# sensorboard_atm_rev0.net
KiCad netlist of a schematic drawn in EAGLE
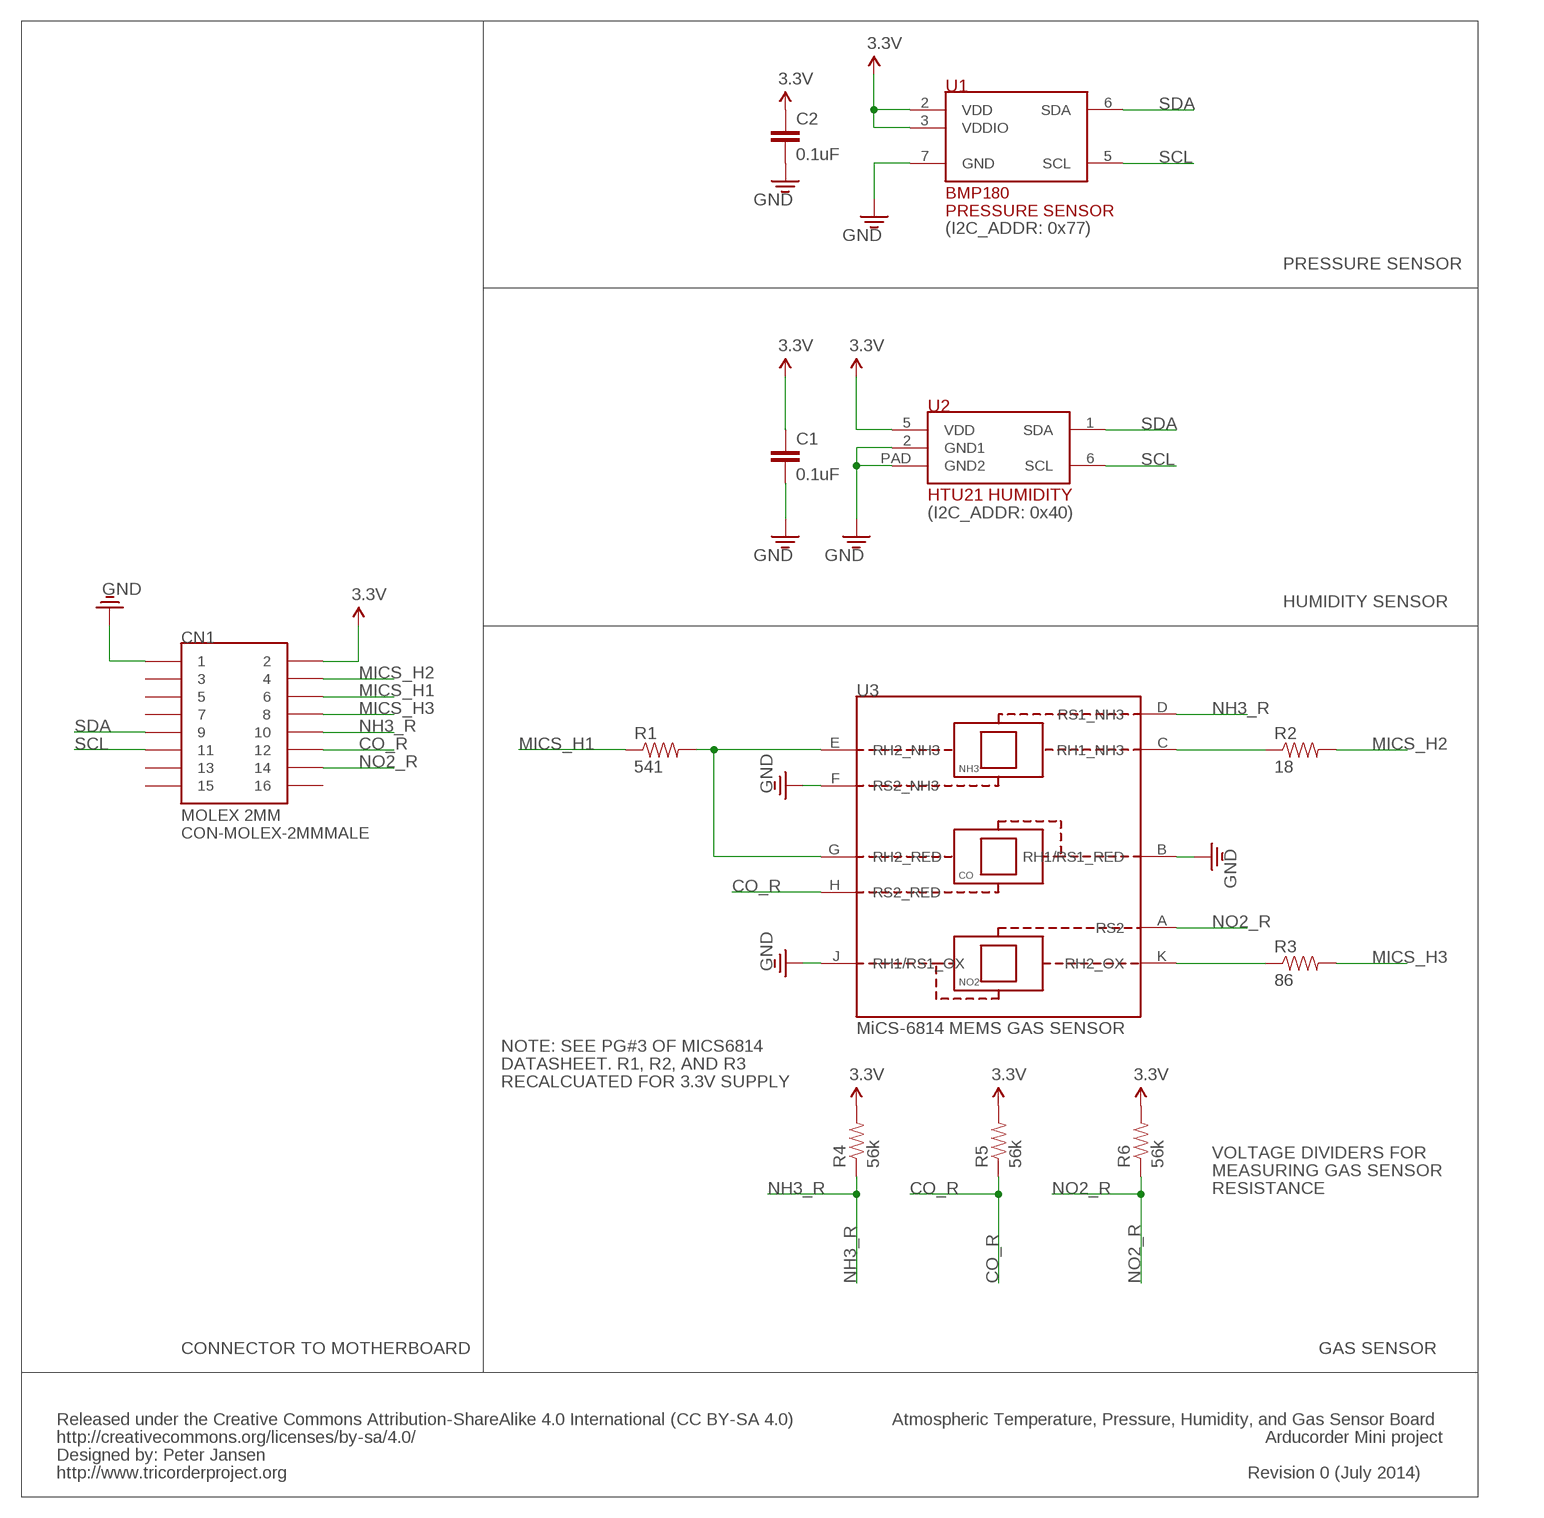
[diagram p0: schematic, sheet 1]

(export (version "E")
  (design (tool "Eeschema 10.0.6"))
  (components
    (comp (ref "C1")
      (value "0.1uF")
      (footprint "eagle-import:0603")
      (libsource (lib "eagle-import") (part "CAP0603"))
    )
    (comp (ref "C2")
      (value "0.1uF")
      (footprint "eagle-import:0603")
      (libsource (lib "eagle-import") (part "CAP0603"))
    )
    (comp (ref "CN1")
      (value "CON-MOLEX-2MMMALE")
      (footprint "eagle-import:MOLEX-0877591650")
      (libsource (lib "eagle-import") (part "CON-MOLEX-2MMMALE"))
    )
    (comp (ref "R1")
      (value "541")
      (footprint "eagle-import:0603")
      (libsource (lib "eagle-import") (part "RESISTOR0603"))
    )
    (comp (ref "R2")
      (value "18")
      (footprint "eagle-import:0603")
      (libsource (lib "eagle-import") (part "RESISTOR0603"))
    )
    (comp (ref "R3")
      (value "86")
      (footprint "eagle-import:0603")
      (libsource (lib "eagle-import") (part "RESISTOR0603"))
    )
    (comp (ref "R4")
      (value "56k")
      (footprint "eagle-import:0603")
      (libsource (lib "eagle-import") (part "RESISTOR0603"))
    )
    (comp (ref "R5")
      (value "56k")
      (footprint "eagle-import:0603")
      (libsource (lib "eagle-import") (part "RESISTOR0603"))
    )
    (comp (ref "R6")
      (value "56k")
      (footprint "eagle-import:0603")
      (libsource (lib "eagle-import") (part "RESISTOR0603"))
    )
    (comp (ref "U1")
      (value "BMP180")
      (footprint "eagle-import:BMP180")
      (libsource (lib "eagle-import") (part "BMP180"))
    )
    (comp (ref "U2")
      (value "HTU21D")
      (footprint "eagle-import:HTU21D")
      (libsource (lib "eagle-import") (part "HTU21D"))
    )
    (comp (ref "U3")
      (value "MICS-6814")
      (footprint "eagle-import:MICS-6814")
      (libsource (lib "eagle-import") (part "MICS-6814"))
    )
  )
  (nets
    (net (code "1") (name "/CO_R") (class "Default")
      (node (ref "CN1") (pin "12") (pinfunction "12_12") (pintype "bidirectional"))
      (node (ref "R5") (pin "1") (pinfunction "1_1") (pintype "passive"))
      (node (ref "U3") (pin "H") (pinfunction "RS2_RED_H") (pintype "bidirectional"))
    )
    (net (code "2") (name "/MICS_H1") (class "Default")
      (node (ref "CN1") (pin "6") (pinfunction "6_6") (pintype "bidirectional"))
      (node (ref "R1") (pin "1") (pinfunction "1_1") (pintype "passive"))
    )
    (net (code "3") (name "/MICS_H2") (class "Default")
      (node (ref "CN1") (pin "4") (pinfunction "4_4") (pintype "bidirectional"))
      (node (ref "R2") (pin "2") (pinfunction "2_2") (pintype "passive"))
    )
    (net (code "4") (name "/MICS_H3") (class "Default")
      (node (ref "CN1") (pin "8") (pinfunction "8_8") (pintype "bidirectional"))
      (node (ref "R3") (pin "2") (pinfunction "2_2") (pintype "passive"))
    )
    (net (code "5") (name "/NH3_R") (class "Default")
      (node (ref "CN1") (pin "10") (pinfunction "10_10") (pintype "bidirectional"))
      (node (ref "R4") (pin "1") (pinfunction "1_1") (pintype "passive"))
      (node (ref "U3") (pin "D") (pinfunction "RS1_NH3_D") (pintype "bidirectional"))
    )
    (net (code "6") (name "/NO2_R") (class "Default")
      (node (ref "CN1") (pin "14") (pinfunction "14_14") (pintype "bidirectional"))
      (node (ref "R6") (pin "1") (pinfunction "1_1") (pintype "passive"))
      (node (ref "U3") (pin "A") (pinfunction "RS2_A") (pintype "bidirectional"))
    )
    (net (code "7") (name "/SCL") (class "Default")
      (node (ref "CN1") (pin "11") (pinfunction "11_11") (pintype "bidirectional"))
      (node (ref "U1") (pin "5") (pinfunction "SCL_5") (pintype "bidirectional"))
      (node (ref "U2") (pin "6") (pinfunction "SCL_6") (pintype "bidirectional"))
    )
    (net (code "8") (name "/SDA") (class "Default")
      (node (ref "CN1") (pin "9") (pinfunction "9_9") (pintype "bidirectional"))
      (node (ref "U1") (pin "6") (pinfunction "SDA_6") (pintype "bidirectional"))
      (node (ref "U2") (pin "1") (pinfunction "SDA_1") (pintype "bidirectional"))
    )
    (net (code "9") (name "3.3V") (class "Default")
      (node (ref "C1") (pin "1") (pinfunction "1_1") (pintype "passive"))
      (node (ref "C2") (pin "1") (pinfunction "1_1") (pintype "passive"))
      (node (ref "CN1") (pin "2") (pinfunction "2_2") (pintype "bidirectional"))
      (node (ref "R4") (pin "2") (pinfunction "2_2") (pintype "passive"))
      (node (ref "R5") (pin "2") (pinfunction "2_2") (pintype "passive"))
      (node (ref "R6") (pin "2") (pinfunction "2_2") (pintype "passive"))
      (node (ref "U1") (pin "2") (pinfunction "VDD_2") (pintype "bidirectional"))
      (node (ref "U1") (pin "3") (pinfunction "VDDIO_3") (pintype "bidirectional"))
      (node (ref "U2") (pin "5") (pinfunction "VDD_5") (pintype "bidirectional"))
    )
    (net (code "10") (name "GND") (class "Default")
      (node (ref "C1") (pin "2") (pinfunction "2_2") (pintype "passive"))
      (node (ref "C2") (pin "2") (pinfunction "2_2") (pintype "passive"))
      (node (ref "CN1") (pin "1") (pinfunction "1_1") (pintype "bidirectional"))
      (node (ref "U1") (pin "7") (pinfunction "GND_7") (pintype "bidirectional"))
      (node (ref "U2") (pin "2") (pinfunction "GND1_2") (pintype "bidirectional"))
      (node (ref "U2") (pin "PAD") (pinfunction "GND2_PAD") (pintype "bidirectional"))
      (node (ref "U3") (pin "B") (pinfunction "RH1/RS1_RED_B") (pintype "bidirectional"))
      (node (ref "U3") (pin "F") (pinfunction "RS2_NH3_F") (pintype "bidirectional"))
      (node (ref "U3") (pin "J") (pinfunction "RH1/RS1_OX_J") (pintype "bidirectional"))
    )
    (net (code "11") (name "Net-(U3-RH1_NH3)") (class "Default")
      (node (ref "R2") (pin "1") (pinfunction "1_1") (pintype "passive"))
      (node (ref "U3") (pin "C") (pinfunction "RH1_NH3_C") (pintype "bidirectional"))
    )
    (net (code "12") (name "Net-(U3-RH2_NH3)") (class "Default")
      (node (ref "R1") (pin "2") (pinfunction "2_2") (pintype "passive"))
      (node (ref "U3") (pin "E") (pinfunction "RH2_NH3_E") (pintype "bidirectional"))
      (node (ref "U3") (pin "G") (pinfunction "RH2_RED_G") (pintype "bidirectional"))
    )
    (net (code "13") (name "Net-(U3-RH2_OX)") (class "Default")
      (node (ref "R3") (pin "1") (pinfunction "1_1") (pintype "passive"))
      (node (ref "U3") (pin "K") (pinfunction "RH2_OX_K") (pintype "bidirectional"))
    )
    (net (code "14") (name "unconnected-(CN1-Pad3)") (class "Default")
      (node (ref "CN1") (pin "3") (pinfunction "3_3") (pintype "bidirectional"))
    )
    (net (code "15") (name "unconnected-(CN1-Pad5)") (class "Default")
      (node (ref "CN1") (pin "5") (pinfunction "5_5") (pintype "bidirectional"))
    )
    (net (code "16") (name "unconnected-(CN1-Pad7)") (class "Default")
      (node (ref "CN1") (pin "7") (pinfunction "7_7") (pintype "bidirectional"))
    )
    (net (code "17") (name "unconnected-(CN1-Pad13)") (class "Default")
      (node (ref "CN1") (pin "13") (pinfunction "13_13") (pintype "bidirectional"))
    )
    (net (code "18") (name "unconnected-(CN1-Pad15)") (class "Default")
      (node (ref "CN1") (pin "15") (pinfunction "15_15") (pintype "bidirectional"))
    )
    (net (code "19") (name "unconnected-(CN1-Pad16)") (class "Default")
      (node (ref "CN1") (pin "16") (pinfunction "16_16") (pintype "bidirectional"))
    )
  )
)
